# B-CAN-giraffe.net
KiCad netlist of a schematic drawn in EAGLE
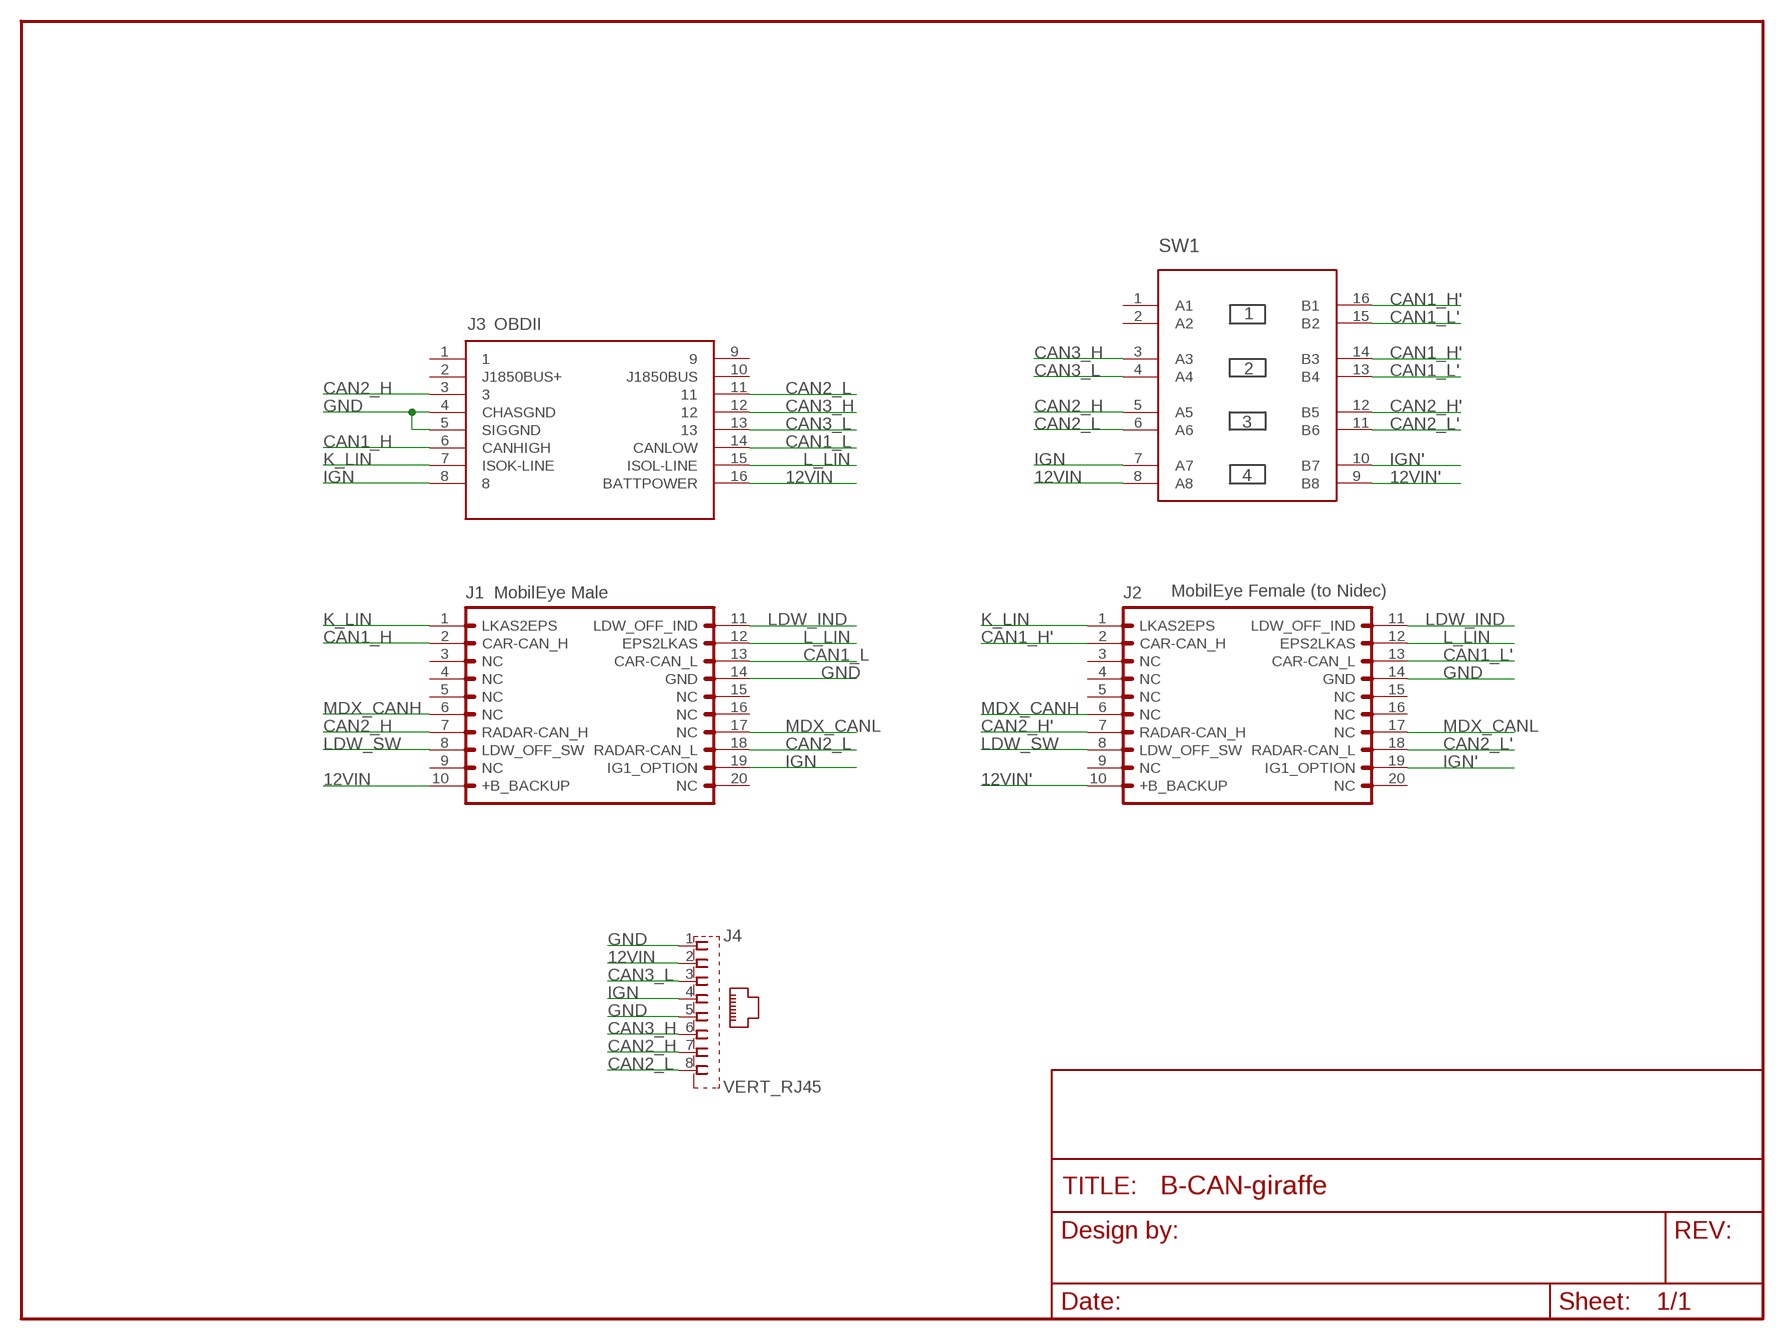
[diagram p0: schematic, sheet 1]

(export (version "E")
  (design (tool "Eeschema 10.0.6"))
  (components
    (comp (ref "FRAME1")
      (value "FRAME-LETTERNO_PACKAGE")
      (footprint "eagle-import:DUMMY")
      (fields (field (name "DESIGNER") "Nobody"))
      (libsource (lib "eagle-import") (part "FRAME-LETTERNO_PACKAGE"))
    )
    (comp (ref "J1")
      (value "MOBILEYERAMALE")
      (footprint "eagle-import:2X10(RA)")
      (libsource (lib "eagle-import") (part "MOBILEYERAMALE"))
    )
    (comp (ref "J2")
      (value "MOBILEYEFEMALE")
      (footprint "eagle-import:2X10(JAE_FEMALE)")
      (libsource (lib "eagle-import") (part "MOBILEYEFEMALE"))
    )
    (comp (ref "J3")
      (value "OBDII-FEMALE-CUT")
      (footprint "eagle-import:OBDII-FEMALE-MIDCUT")
      (libsource (lib "eagle-import") (part "OBDII-FEMALE-CUT"))
    )
    (comp (ref "J4")
      (value "VERT_RJ45")
      (footprint "eagle-import:GLX-S-88M")
      (libsource (lib "eagle-import") (part "VERT_RJ45"))
    )
    (comp (ref "SW1")
      (value "4XDPSTSMT")
      (footprint "eagle-import:4-DPST")
      (libsource (lib "eagle-import") (part "4XDPSTSMT"))
    )
  )
  (nets
    (net (code "1") (name "/12VIN") (class "Default")
      (node (ref "J1") (pin "10") (pinfunction "+B_BACKUP_10") (pintype "bidirectional"))
      (node (ref "J3") (pin "16") (pinfunction "BATTPOWER_16") (pintype "bidirectional"))
      (node (ref "J4") (pin "2") (pinfunction "2_2") (pintype "passive"))
      (node (ref "SW1") (pin "8") (pinfunction "A8_8") (pintype "bidirectional"))
    )
    (net (code "2") (name "/12VIN'") (class "Default")
      (node (ref "J2") (pin "10") (pinfunction "+B_BACKUP_10") (pintype "bidirectional"))
      (node (ref "SW1") (pin "9") (pinfunction "B8_9") (pintype "bidirectional"))
    )
    (net (code "3") (name "/CAN1_H") (class "Default")
      (node (ref "J1") (pin "2") (pinfunction "CAR-CAN_H_2") (pintype "bidirectional"))
      (node (ref "J3") (pin "6") (pinfunction "CANHIGH_6") (pintype "bidirectional"))
    )
    (net (code "4") (name "/CAN1_H'") (class "Default")
      (node (ref "J2") (pin "2") (pinfunction "CAR-CAN_H_2") (pintype "bidirectional"))
      (node (ref "SW1") (pin "14") (pinfunction "B3_14") (pintype "bidirectional"))
      (node (ref "SW1") (pin "16") (pinfunction "B1_16") (pintype "bidirectional"))
    )
    (net (code "5") (name "/CAN1_L") (class "Default")
      (node (ref "J1") (pin "13") (pinfunction "CAR-CAN_L_13") (pintype "bidirectional"))
      (node (ref "J3") (pin "14") (pinfunction "CANLOW_14") (pintype "bidirectional"))
    )
    (net (code "6") (name "/CAN1_L'") (class "Default")
      (node (ref "J2") (pin "13") (pinfunction "CAR-CAN_L_13") (pintype "bidirectional"))
      (node (ref "SW1") (pin "13") (pinfunction "B4_13") (pintype "bidirectional"))
      (node (ref "SW1") (pin "15") (pinfunction "B2_15") (pintype "bidirectional"))
    )
    (net (code "7") (name "/CAN2_H") (class "Default")
      (node (ref "J1") (pin "7") (pinfunction "RADAR-CAN_H_7") (pintype "bidirectional"))
      (node (ref "J3") (pin "3") (pinfunction "3_3") (pintype "bidirectional"))
      (node (ref "J4") (pin "7") (pinfunction "7_7") (pintype "passive"))
      (node (ref "SW1") (pin "5") (pinfunction "A5_5") (pintype "bidirectional"))
    )
    (net (code "8") (name "/CAN2_H'") (class "Default")
      (node (ref "J2") (pin "7") (pinfunction "RADAR-CAN_H_7") (pintype "bidirectional"))
      (node (ref "SW1") (pin "12") (pinfunction "B5_12") (pintype "bidirectional"))
    )
    (net (code "9") (name "/CAN2_L") (class "Default")
      (node (ref "J1") (pin "18") (pinfunction "RADAR-CAN_L_18") (pintype "bidirectional"))
      (node (ref "J3") (pin "11") (pinfunction "11_11") (pintype "bidirectional"))
      (node (ref "J4") (pin "8") (pinfunction "8_8") (pintype "passive"))
      (node (ref "SW1") (pin "6") (pinfunction "A6_6") (pintype "bidirectional"))
    )
    (net (code "10") (name "/CAN2_L'") (class "Default")
      (node (ref "J2") (pin "18") (pinfunction "RADAR-CAN_L_18") (pintype "bidirectional"))
      (node (ref "SW1") (pin "11") (pinfunction "B6_11") (pintype "bidirectional"))
    )
    (net (code "11") (name "/CAN3_H") (class "Default")
      (node (ref "J3") (pin "12") (pinfunction "12_12") (pintype "bidirectional"))
      (node (ref "J4") (pin "6") (pinfunction "6_6") (pintype "passive"))
      (node (ref "SW1") (pin "3") (pinfunction "A3_3") (pintype "bidirectional"))
    )
    (net (code "12") (name "/CAN3_L") (class "Default")
      (node (ref "J3") (pin "13") (pinfunction "13_13") (pintype "bidirectional"))
      (node (ref "J4") (pin "3") (pinfunction "3_3") (pintype "passive"))
      (node (ref "SW1") (pin "4") (pinfunction "A4_4") (pintype "bidirectional"))
    )
    (net (code "13") (name "/GND") (class "Default")
      (node (ref "J1") (pin "14") (pinfunction "GND_14") (pintype "bidirectional"))
      (node (ref "J2") (pin "14") (pinfunction "GND_14") (pintype "bidirectional"))
      (node (ref "J3") (pin "4") (pinfunction "CHASGND_4") (pintype "bidirectional"))
      (node (ref "J3") (pin "5") (pinfunction "SIGGND_5") (pintype "bidirectional"))
      (node (ref "J4") (pin "1") (pinfunction "1_1") (pintype "passive"))
      (node (ref "J4") (pin "5") (pinfunction "5_5") (pintype "passive"))
    )
    (net (code "14") (name "/IGN") (class "Default")
      (node (ref "J1") (pin "19") (pinfunction "IG1_OPTION_19") (pintype "bidirectional"))
      (node (ref "J3") (pin "8") (pinfunction "8_8") (pintype "bidirectional"))
      (node (ref "J4") (pin "4") (pinfunction "4_4") (pintype "passive"))
      (node (ref "SW1") (pin "7") (pinfunction "A7_7") (pintype "bidirectional"))
    )
    (net (code "15") (name "/IGN'") (class "Default")
      (node (ref "J2") (pin "19") (pinfunction "IG1_OPTION_19") (pintype "bidirectional"))
      (node (ref "SW1") (pin "10") (pinfunction "B7_10") (pintype "bidirectional"))
    )
    (net (code "16") (name "/K_LIN") (class "Default")
      (node (ref "J1") (pin "1") (pinfunction "LKAS2EPS_1") (pintype "bidirectional"))
      (node (ref "J2") (pin "1") (pinfunction "LKAS2EPS_1") (pintype "bidirectional"))
      (node (ref "J3") (pin "7") (pinfunction "ISOK-LINE_7") (pintype "bidirectional"))
    )
    (net (code "17") (name "/LDW_IND") (class "Default")
      (node (ref "J1") (pin "11") (pinfunction "LDW_OFF_IND_11") (pintype "bidirectional"))
      (node (ref "J2") (pin "11") (pinfunction "LDW_OFF_IND_11") (pintype "bidirectional"))
    )
    (net (code "18") (name "/LDW_SW") (class "Default")
      (node (ref "J1") (pin "8") (pinfunction "LDW_OFF_SW_8") (pintype "bidirectional"))
      (node (ref "J2") (pin "8") (pinfunction "LDW_OFF_SW_8") (pintype "bidirectional"))
    )
    (net (code "19") (name "/L_LIN") (class "Default")
      (node (ref "J1") (pin "12") (pinfunction "EPS2LKAS_12") (pintype "bidirectional"))
      (node (ref "J2") (pin "12") (pinfunction "EPS2LKAS_12") (pintype "bidirectional"))
      (node (ref "J3") (pin "15") (pinfunction "ISOL-LINE_15") (pintype "bidirectional"))
    )
    (net (code "20") (name "/MDX_CANH") (class "Default")
      (node (ref "J1") (pin "6") (pinfunction "NC_6") (pintype "bidirectional"))
      (node (ref "J2") (pin "6") (pinfunction "NC_6") (pintype "bidirectional"))
    )
    (net (code "21") (name "/MDX_CANL") (class "Default")
      (node (ref "J1") (pin "17") (pinfunction "NC_17") (pintype "bidirectional"))
      (node (ref "J2") (pin "17") (pinfunction "NC_17") (pintype "bidirectional"))
    )
    (net (code "22") (name "unconnected-(J1-NC-Pad3)") (class "Default")
      (node (ref "J1") (pin "3") (pinfunction "NC_3") (pintype "bidirectional"))
    )
    (net (code "23") (name "unconnected-(J1-NC-Pad4)") (class "Default")
      (node (ref "J1") (pin "4") (pinfunction "NC_4") (pintype "bidirectional"))
    )
    (net (code "24") (name "unconnected-(J1-NC-Pad5)") (class "Default")
      (node (ref "J1") (pin "5") (pinfunction "NC_5") (pintype "bidirectional"))
    )
    (net (code "25") (name "unconnected-(J1-NC-Pad9)") (class "Default")
      (node (ref "J1") (pin "9") (pinfunction "NC_9") (pintype "bidirectional"))
    )
    (net (code "26") (name "unconnected-(J1-NC-Pad15)") (class "Default")
      (node (ref "J1") (pin "15") (pinfunction "NC_15") (pintype "bidirectional"))
    )
    (net (code "27") (name "unconnected-(J1-NC-Pad16)") (class "Default")
      (node (ref "J1") (pin "16") (pinfunction "NC_16") (pintype "bidirectional"))
    )
    (net (code "28") (name "unconnected-(J1-NC-Pad20)") (class "Default")
      (node (ref "J1") (pin "20") (pinfunction "NC_20") (pintype "bidirectional"))
    )
    (net (code "29") (name "unconnected-(J2-NC-Pad3)") (class "Default")
      (node (ref "J2") (pin "3") (pinfunction "NC_3") (pintype "bidirectional"))
    )
    (net (code "30") (name "unconnected-(J2-NC-Pad4)") (class "Default")
      (node (ref "J2") (pin "4") (pinfunction "NC_4") (pintype "bidirectional"))
    )
    (net (code "31") (name "unconnected-(J2-NC-Pad5)") (class "Default")
      (node (ref "J2") (pin "5") (pinfunction "NC_5") (pintype "bidirectional"))
    )
    (net (code "32") (name "unconnected-(J2-NC-Pad9)") (class "Default")
      (node (ref "J2") (pin "9") (pinfunction "NC_9") (pintype "bidirectional"))
    )
    (net (code "33") (name "unconnected-(J2-NC-Pad15)") (class "Default")
      (node (ref "J2") (pin "15") (pinfunction "NC_15") (pintype "bidirectional"))
    )
    (net (code "34") (name "unconnected-(J2-NC-Pad16)") (class "Default")
      (node (ref "J2") (pin "16") (pinfunction "NC_16") (pintype "bidirectional"))
    )
    (net (code "35") (name "unconnected-(J2-NC-Pad20)") (class "Default")
      (node (ref "J2") (pin "20") (pinfunction "NC_20") (pintype "bidirectional"))
    )
    (net (code "36") (name "unconnected-(J3-J1850BUS+-Pad2)") (class "Default")
      (node (ref "J3") (pin "2") (pinfunction "J1850BUS+_2") (pintype "bidirectional"))
    )
    (net (code "37") (name "unconnected-(J3-J1850BUS-Pad10)") (class "Default")
      (node (ref "J3") (pin "10") (pinfunction "J1850BUS_10") (pintype "bidirectional"))
    )
    (net (code "38") (name "unconnected-(J3-Pad1)") (class "Default")
      (node (ref "J3") (pin "1") (pinfunction "1_1") (pintype "bidirectional"))
    )
    (net (code "39") (name "unconnected-(J3-Pad9)") (class "Default")
      (node (ref "J3") (pin "9") (pinfunction "9_9") (pintype "bidirectional"))
    )
    (net (code "40") (name "unconnected-(SW1-A1-Pad1)") (class "Default")
      (node (ref "SW1") (pin "1") (pinfunction "A1_1") (pintype "bidirectional"))
    )
    (net (code "41") (name "unconnected-(SW1-A2-Pad2)") (class "Default")
      (node (ref "SW1") (pin "2") (pinfunction "A2_2") (pintype "bidirectional"))
    )
  )
)
